# ADC_Chip.net
KiCad netlist of a schematic drawn in Altium Designer
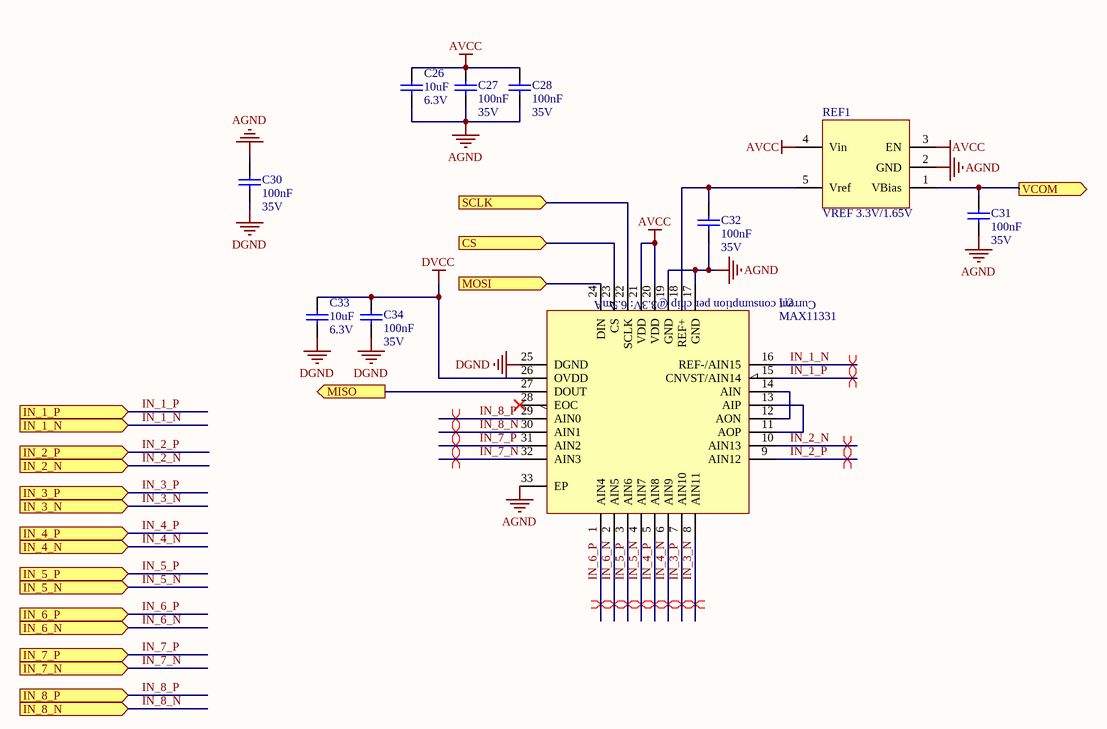
[diagram p0: ADC Chip.SchDoc]

(export (version "E")
  (design (tool "Eeschema 10.0.6"))
  (components
    (comp (ref "C26")
      (value "10uF")
      (footprint "CAP_0603")
      (description "Capacitor Ceramic")
      (fields
        (field (name "MPN") "JMK107ABJ106MA-T")
        (field (name "VOLTAGE") "6.3V")
        (field (name "MF") "Tayo Yuden")
      )
      (libsource (lib "Componentes_SOC") (part "Cap_0603"))
    )
    (comp (ref "C27")
      (value "100nF")
      (footprint "CAP_0603")
      (description "Capacitor")
      (fields
        (field (name "MPN") "C0603C104M5RACTU")
        (field (name "MF") "KEMET")
        (field (name "VOLTAGE") "35V")
        (field (name "PUBLISHER") "Altium Limited")
      )
      (libsource (lib "Componentes_SOC") (part "Cap_0603"))
    )
    (comp (ref "C28")
      (value "100nF")
      (footprint "CAP_0603")
      (description "Capacitor")
      (fields
        (field (name "MPN") "C0603C104M5RACTU")
        (field (name "MF") "KEMET")
        (field (name "VOLTAGE") "35V")
        (field (name "PUBLISHER") "Altium Limited")
      )
      (libsource (lib "Componentes_SOC") (part "Cap_0603"))
    )
    (comp (ref "C30")
      (value "100nF")
      (footprint "CAP_0603")
      (description "Capacitor")
      (fields
        (field (name "MPN") "C0603C104M5RACTU")
        (field (name "MF") "KEMET")
        (field (name "VOLTAGE") "35V")
        (field (name "PUBLISHER") "Altium Limited")
      )
      (libsource (lib "Componentes_SOC") (part "Cap_0603"))
    )
    (comp (ref "C31")
      (value "100nF")
      (footprint "CAP_0603")
      (description "Capacitor")
      (fields
        (field (name "MPN") "C0603C104M5RACTU")
        (field (name "MF") "KEMET")
        (field (name "VOLTAGE") "35V")
        (field (name "PUBLISHER") "Altium Limited")
      )
      (libsource (lib "Componentes_SOC") (part "Cap_0603"))
    )
    (comp (ref "C32")
      (value "100nF")
      (footprint "CAP_0603")
      (description "Capacitor")
      (fields
        (field (name "MPN") "C0603C104M5RACTU")
        (field (name "MF") "KEMET")
        (field (name "VOLTAGE") "35V")
        (field (name "PUBLISHER") "Altium Limited")
      )
      (libsource (lib "Componentes_SOC") (part "Cap_0603"))
    )
    (comp (ref "C33")
      (value "10uF")
      (footprint "CAP_0603")
      (description "Capacitor Ceramic")
      (fields
        (field (name "MPN") "JMK107ABJ106MA-T")
        (field (name "VOLTAGE") "6.3V")
        (field (name "MF") "Tayo Yuden")
      )
      (libsource (lib "Componentes_SOC") (part "Cap_0603"))
    )
    (comp (ref "C34")
      (value "100nF")
      (footprint "CAP_0603")
      (description "Capacitor")
      (fields
        (field (name "MPN") "C0603C104M5RACTU")
        (field (name "MF") "KEMET")
        (field (name "VOLTAGE") "35V")
        (field (name "PUBLISHER") "Altium Limited")
      )
      (libsource (lib "Componentes_SOC") (part "Cap_0603"))
    )
    (comp (ref "REF1")
      (value "VREF 3.3V/1.65V")
      (footprint "SOT-23-5")
      (fields
        (field (name "MPN") "REF2033AIDDCT")
        (field (name "MF") "Texas Instruments")
        (field (name "LCSC PART NUMBER") "C181409")
      )
      (libsource (lib "Componentes_SOC") (part "VREF 3.3V/1.65V"))
    )
    (comp (ref "U2")
      (value "MAX11331")
      (footprint "QFN50P500X500X80-33N-310")
      (description "ADC 12 bits SPI")
      (fields (field (name "LCSC PART NUMBER") "C1543252"))
      (libsource (lib "Componentes_SOC") (part "MAX11331"))
    )
  )
  (nets
    (net (code "1") (name "/CS") (class "Default")
      (node (ref "U2") (pin "23") (pinfunction "CS_23") (pintype "passive"))
    )
    (net (code "2") (name "/IN_1_N") (class "Default")
      (node (ref "U2") (pin "16") (pinfunction "REF-/AIN15_16") (pintype "passive"))
    )
    (net (code "3") (name "/IN_1_P") (class "Default")
      (node (ref "U2") (pin "15") (pinfunction "CNVST/AIN14_15") (pintype "passive"))
    )
    (net (code "4") (name "/IN_2_N") (class "Default")
      (node (ref "U2") (pin "10") (pinfunction "AIN13_10") (pintype "passive"))
    )
    (net (code "5") (name "/IN_2_P") (class "Default")
      (node (ref "U2") (pin "9") (pinfunction "AIN12_9") (pintype "passive"))
    )
    (net (code "6") (name "/IN_3_N") (class "Default")
      (node (ref "U2") (pin "8") (pinfunction "AIN11_8") (pintype "passive"))
    )
    (net (code "7") (name "/IN_3_P") (class "Default")
      (node (ref "U2") (pin "7") (pinfunction "AIN10_7") (pintype "passive"))
    )
    (net (code "8") (name "/IN_4_N") (class "Default")
      (node (ref "U2") (pin "6") (pinfunction "AIN9_6") (pintype "passive"))
    )
    (net (code "9") (name "/IN_4_P") (class "Default")
      (node (ref "U2") (pin "5") (pinfunction "AIN8_5") (pintype "passive"))
    )
    (net (code "10") (name "/IN_5_N") (class "Default")
      (node (ref "U2") (pin "4") (pinfunction "AIN7_4") (pintype "passive"))
    )
    (net (code "11") (name "/IN_5_P") (class "Default")
      (node (ref "U2") (pin "3") (pinfunction "AIN6_3") (pintype "passive"))
    )
    (net (code "12") (name "/IN_6_N") (class "Default")
      (node (ref "U2") (pin "2") (pinfunction "AIN5_2") (pintype "passive"))
    )
    (net (code "13") (name "/IN_6_P") (class "Default")
      (node (ref "U2") (pin "1") (pinfunction "AIN4_1") (pintype "passive"))
    )
    (net (code "14") (name "/IN_7_N") (class "Default")
      (node (ref "U2") (pin "32") (pinfunction "AIN3_32") (pintype "passive"))
    )
    (net (code "15") (name "/IN_7_P") (class "Default")
      (node (ref "U2") (pin "31") (pinfunction "AIN2_31") (pintype "passive"))
    )
    (net (code "16") (name "/IN_8_N") (class "Default")
      (node (ref "U2") (pin "30") (pinfunction "AIN1_30") (pintype "passive"))
    )
    (net (code "17") (name "/IN_8_P") (class "Default")
      (node (ref "U2") (pin "29") (pinfunction "AIN0_29") (pintype "passive"))
    )
    (net (code "18") (name "/MISO") (class "Default")
      (node (ref "U2") (pin "27") (pinfunction "DOUT_27") (pintype "passive"))
    )
    (net (code "19") (name "/MOSI") (class "Default")
      (node (ref "U2") (pin "24") (pinfunction "DIN_24") (pintype "passive"))
    )
    (net (code "20") (name "/SCLK") (class "Default")
      (node (ref "U2") (pin "22") (pinfunction "SCLK_22") (pintype "passive"))
    )
    (net (code "21") (name "/VCOM") (class "Default")
      (node (ref "C31") (pin "1") (pinfunction "1_1") (pintype "passive"))
      (node (ref "REF1") (pin "1") (pinfunction "VBias_1") (pintype "passive"))
    )
    (net (code "22") (name "AGND") (class "Default")
      (node (ref "C26") (pin "2") (pinfunction "2_2") (pintype "passive"))
      (node (ref "C27") (pin "2") (pinfunction "2_2") (pintype "passive"))
      (node (ref "C28") (pin "2") (pinfunction "2_2") (pintype "passive"))
      (node (ref "C30") (pin "1") (pinfunction "1_1") (pintype "passive"))
      (node (ref "C31") (pin "2") (pinfunction "2_2") (pintype "passive"))
      (node (ref "C32") (pin "2") (pinfunction "2_2") (pintype "passive"))
      (node (ref "REF1") (pin "2") (pinfunction "GND_2") (pintype "passive"))
      (node (ref "U2") (pin "17") (pinfunction "GND_17") (pintype "passive"))
      (node (ref "U2") (pin "19") (pinfunction "GND_19") (pintype "passive"))
      (node (ref "U2") (pin "33") (pinfunction "EP_33") (pintype "passive"))
    )
    (net (code "23") (name "AVCC") (class "Default")
      (node (ref "C26") (pin "1") (pinfunction "1_1") (pintype "passive"))
      (node (ref "C27") (pin "1") (pinfunction "1_1") (pintype "passive"))
      (node (ref "C28") (pin "1") (pinfunction "1_1") (pintype "passive"))
      (node (ref "REF1") (pin "3") (pinfunction "EN_3") (pintype "passive"))
      (node (ref "REF1") (pin "4") (pinfunction "Vin_4") (pintype "passive"))
      (node (ref "U2") (pin "20") (pinfunction "VDD_20") (pintype "passive"))
      (node (ref "U2") (pin "21") (pinfunction "VDD_21") (pintype "passive"))
    )
    (net (code "24") (name "DGND") (class "Default")
      (node (ref "C30") (pin "2") (pinfunction "2_2") (pintype "passive"))
      (node (ref "C33") (pin "2") (pinfunction "2_2") (pintype "passive"))
      (node (ref "C34") (pin "2") (pinfunction "2_2") (pintype "passive"))
      (node (ref "U2") (pin "25") (pinfunction "DGND_25") (pintype "passive"))
    )
    (net (code "25") (name "DVCC") (class "Default")
      (node (ref "C33") (pin "1") (pinfunction "1_1") (pintype "passive"))
      (node (ref "C34") (pin "1") (pinfunction "1_1") (pintype "passive"))
      (node (ref "U2") (pin "26") (pinfunction "OVDD_26") (pintype "passive"))
    )
    (net (code "26") (name "Net-(REF1-Vref)") (class "Default")
      (node (ref "C32") (pin "1") (pinfunction "1_1") (pintype "passive"))
      (node (ref "REF1") (pin "5") (pinfunction "Vref_5") (pintype "passive"))
      (node (ref "U2") (pin "18") (pinfunction "REF+_18") (pintype "passive"))
    )
    (net (code "27") (name "Net-(U2-AIN)") (class "Default")
      (node (ref "U2") (pin "12") (pinfunction "AON_12") (pintype "passive"))
      (node (ref "U2") (pin "14") (pinfunction "AIN_14") (pintype "passive"))
    )
    (net (code "28") (name "Net-(U2-AIP)") (class "Default")
      (node (ref "U2") (pin "11") (pinfunction "AOP_11") (pintype "passive"))
      (node (ref "U2") (pin "13") (pinfunction "AIP_13") (pintype "passive"))
    )
    (net (code "29") (name "unconnected-(U2-EOC-Pad28)") (class "Default")
      (node (ref "U2") (pin "28") (pinfunction "EOC_28") (pintype "passive+no_connect"))
    )
  )
)
